# incandescentDriver.net
KiCad netlist of a schematic drawn in EAGLE
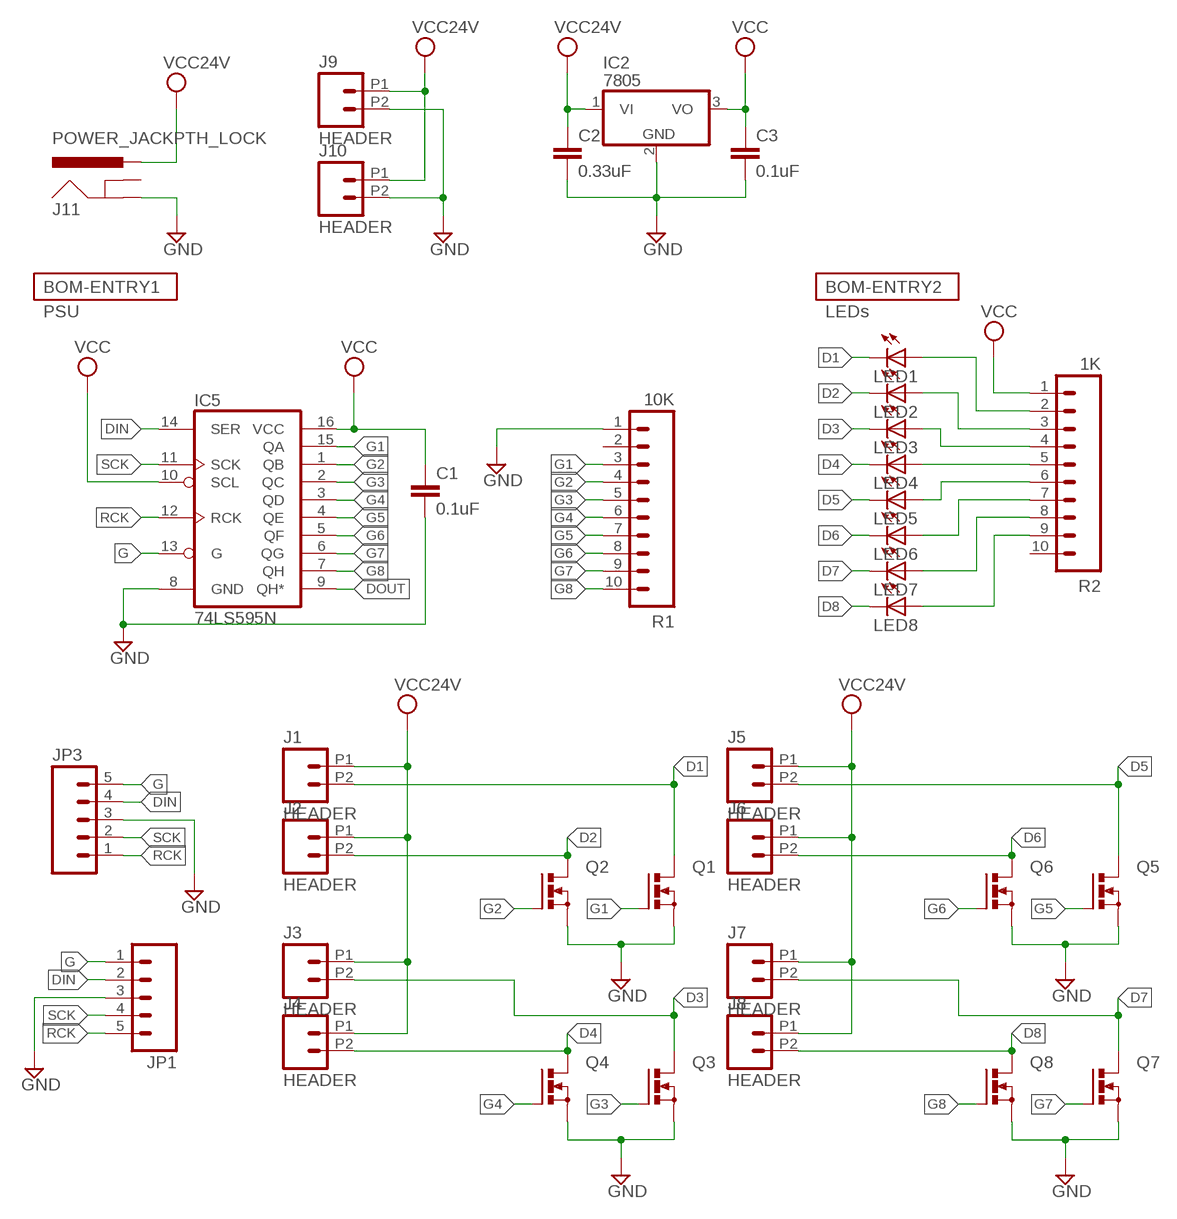
[diagram p0: schematic, sheet 1]

(export (version "E")
  (design (tool "Eeschema 10.0.6"))
  (components
    (comp (ref "C1")
      (value "0.1uF")
      (footprint "eagle-import:CAP-PTH-SMALL")
      (fields (field (name "PARTNO") "SR295E104MAR"))
      (libsource (lib "eagle-import") (part "CAPPTH"))
    )
    (comp (ref "C2")
      (value "0.33uF")
      (footprint "eagle-import:CAP-PTH-SMALL")
      (fields (field (name "PARTNO") "FK24X7R1H334K"))
      (libsource (lib "eagle-import") (part "CAPPTH"))
    )
    (comp (ref "C3")
      (value "0.1uF")
      (footprint "eagle-import:CAP-PTH-SMALL")
      (fields (field (name "PARTNO") "SR295E104MAR"))
      (libsource (lib "eagle-import") (part "CAPPTH"))
    )
    (comp (ref "IC2")
      (value "7805")
      (footprint "eagle-import:TO220V")
      (fields (field (name "PARTNO") "NCP7805TG"))
      (libsource (lib "eagle-import") (part "78TV8"))
    )
    (comp (ref "IC5")
      (value "74LS595N")
      (footprint "eagle-import:DIL16")
      (fields (field (name "PARTNO") "SN74HC164N"))
      (libsource (lib "eagle-import") (part "74595NLS"))
    )
    (comp (ref "J1")
      (value "HEADER")
      (footprint "eagle-import:1X02-5.08-SCREWTERM")
      (fields (field (name "PARTNO") "OSTTC022162"))
      (libsource (lib "eagle-import") (part "HEADER"))
    )
    (comp (ref "J2")
      (value "HEADER")
      (footprint "eagle-import:1X02-5.08-SCREWTERM")
      (fields (field (name "PARTNO") "OSTTC022162"))
      (libsource (lib "eagle-import") (part "HEADER"))
    )
    (comp (ref "J3")
      (value "HEADER")
      (footprint "eagle-import:1X02-5.08-SCREWTERM")
      (fields (field (name "PARTNO") "OSTTC022162"))
      (libsource (lib "eagle-import") (part "HEADER"))
    )
    (comp (ref "J4")
      (value "HEADER")
      (footprint "eagle-import:1X02-5.08-SCREWTERM")
      (fields (field (name "PARTNO") "OSTTC022162"))
      (libsource (lib "eagle-import") (part "HEADER"))
    )
    (comp (ref "J5")
      (value "HEADER")
      (footprint "eagle-import:1X02-5.08-SCREWTERM")
      (fields (field (name "PARTNO") "OSTTC022162"))
      (libsource (lib "eagle-import") (part "HEADER"))
    )
    (comp (ref "J6")
      (value "HEADER")
      (footprint "eagle-import:1X02-5.08-SCREWTERM")
      (fields (field (name "PARTNO") "OSTTC022162"))
      (libsource (lib "eagle-import") (part "HEADER"))
    )
    (comp (ref "J7")
      (value "HEADER")
      (footprint "eagle-import:1X02-5.08-SCREWTERM")
      (fields (field (name "PARTNO") "OSTTC022162"))
      (libsource (lib "eagle-import") (part "HEADER"))
    )
    (comp (ref "J8")
      (value "HEADER")
      (footprint "eagle-import:1X02-5.08-SCREWTERM")
      (fields (field (name "PARTNO") "OSTTC022162"))
      (libsource (lib "eagle-import") (part "HEADER"))
    )
    (comp (ref "J9")
      (value "HEADER")
      (footprint "eagle-import:1X02-5.08-SCREWTERM")
      (fields (field (name "PARTNO") "OSTTC022162"))
      (libsource (lib "eagle-import") (part "HEADER"))
    )
    (comp (ref "J10")
      (value "HEADER")
      (footprint "eagle-import:1X02-5.08-SCREWTERM")
      (fields (field (name "PARTNO") "OSTTC022162"))
      (libsource (lib "eagle-import") (part "HEADER"))
    )
    (comp (ref "J11")
      (value "POWER_JACKPTH_LOCK")
      (footprint "eagle-import:POWER_JACK_PTH_LOCK")
      (fields (field (name "PARTNO") "PJ-202A"))
      (libsource (lib "eagle-import") (part "POWER_JACKPTH_LOCK"))
    )
    (comp (ref "JP1")
      (value "M05LOCK")
      (footprint "eagle-import:1X05_LOCK")
      (fields (field (name "PARTNO") "M20-9960545"))
      (libsource (lib "eagle-import") (part "M05LOCK"))
    )
    (comp (ref "JP3")
      (value "M05LOCK")
      (footprint "eagle-import:1X05_LOCK")
      (fields (field (name "PARTNO") "M20-9960545"))
      (libsource (lib "eagle-import") (part "M05LOCK"))
    )
    (comp (ref "LED1")
      (value "LED5MM")
      (footprint "eagle-import:LED5MM")
      (libsource (lib "eagle-import") (part "LED5MM"))
    )
    (comp (ref "LED2")
      (value "LED5MM")
      (footprint "eagle-import:LED5MM")
      (libsource (lib "eagle-import") (part "LED5MM"))
    )
    (comp (ref "LED3")
      (value "LED5MM")
      (footprint "eagle-import:LED5MM")
      (libsource (lib "eagle-import") (part "LED5MM"))
    )
    (comp (ref "LED4")
      (value "LED5MM")
      (footprint "eagle-import:LED5MM")
      (libsource (lib "eagle-import") (part "LED5MM"))
    )
    (comp (ref "LED5")
      (value "LED5MM")
      (footprint "eagle-import:LED5MM")
      (libsource (lib "eagle-import") (part "LED5MM"))
    )
    (comp (ref "LED6")
      (value "LED5MM")
      (footprint "eagle-import:LED5MM")
      (libsource (lib "eagle-import") (part "LED5MM"))
    )
    (comp (ref "LED7")
      (value "LED5MM")
      (footprint "eagle-import:LED5MM")
      (libsource (lib "eagle-import") (part "LED5MM"))
    )
    (comp (ref "LED8")
      (value "LED5MM")
      (footprint "eagle-import:LED5MM")
      (libsource (lib "eagle-import") (part "LED5MM"))
    )
    (comp (ref "Q1")
      (value "PMOSFET_NTO220BV")
      (footprint "eagle-import:TO220BV")
      (fields (field (name "PARTNO") "FQP13N10L"))
      (libsource (lib "eagle-import") (part "PMOSFET_NTO220BV"))
    )
    (comp (ref "Q2")
      (value "PMOSFET_NTO220BV")
      (footprint "eagle-import:TO220BV")
      (fields (field (name "PARTNO") "FQP13N10L"))
      (libsource (lib "eagle-import") (part "PMOSFET_NTO220BV"))
    )
    (comp (ref "Q3")
      (value "PMOSFET_NTO220BV")
      (footprint "eagle-import:TO220BV")
      (fields (field (name "PARTNO") "FQP13N10L"))
      (libsource (lib "eagle-import") (part "PMOSFET_NTO220BV"))
    )
    (comp (ref "Q4")
      (value "PMOSFET_NTO220BV")
      (footprint "eagle-import:TO220BV")
      (fields (field (name "PARTNO") "FQP13N10L"))
      (libsource (lib "eagle-import") (part "PMOSFET_NTO220BV"))
    )
    (comp (ref "Q5")
      (value "PMOSFET_NTO220BV")
      (footprint "eagle-import:TO220BV")
      (fields (field (name "PARTNO") "FQP13N10L"))
      (libsource (lib "eagle-import") (part "PMOSFET_NTO220BV"))
    )
    (comp (ref "Q6")
      (value "PMOSFET_NTO220BV")
      (footprint "eagle-import:TO220BV")
      (fields (field (name "PARTNO") "FQP13N10L"))
      (libsource (lib "eagle-import") (part "PMOSFET_NTO220BV"))
    )
    (comp (ref "Q7")
      (value "PMOSFET_NTO220BV")
      (footprint "eagle-import:TO220BV")
      (fields (field (name "PARTNO") "FQP13N10L"))
      (libsource (lib "eagle-import") (part "PMOSFET_NTO220BV"))
    )
    (comp (ref "Q8")
      (value "PMOSFET_NTO220BV")
      (footprint "eagle-import:TO220BV")
      (fields (field (name "PARTNO") "FQP13N10L"))
      (libsource (lib "eagle-import") (part "PMOSFET_NTO220BV"))
    )
    (comp (ref "R1")
      (value "10K")
      (footprint "eagle-import:1X10_LOCK")
      (fields (field (name "PARTNO") "L101S103LF"))
      (libsource (lib "eagle-import") (part "M10LOCK"))
    )
    (comp (ref "R2")
      (value "1K")
      (footprint "eagle-import:1X10_LOCK")
      (fields (field (name "PARTNO") "4609X-101-102LF"))
      (libsource (lib "eagle-import") (part "M10LOCK"))
    )
  )
  (nets
    (net (code "1") (name "D1") (class "Default")
      (node (ref "J1") (pin "P2") (pinfunction "1_P2") (pintype "passive"))
      (node (ref "LED1") (pin "K") (pinfunction "C_K") (pintype "passive"))
      (node (ref "Q1") (pin "D") (pinfunction "D_D") (pintype "passive"))
    )
    (net (code "2") (name "D2") (class "Default")
      (node (ref "J2") (pin "P2") (pinfunction "1_P2") (pintype "passive"))
      (node (ref "LED2") (pin "K") (pinfunction "C_K") (pintype "passive"))
      (node (ref "Q2") (pin "D") (pinfunction "D_D") (pintype "passive"))
    )
    (net (code "3") (name "D3") (class "Default")
      (node (ref "J3") (pin "P2") (pinfunction "1_P2") (pintype "passive"))
      (node (ref "LED3") (pin "K") (pinfunction "C_K") (pintype "passive"))
      (node (ref "Q3") (pin "D") (pinfunction "D_D") (pintype "passive"))
    )
    (net (code "4") (name "D4") (class "Default")
      (node (ref "J4") (pin "P2") (pinfunction "1_P2") (pintype "passive"))
      (node (ref "LED4") (pin "K") (pinfunction "C_K") (pintype "passive"))
      (node (ref "Q4") (pin "D") (pinfunction "D_D") (pintype "passive"))
    )
    (net (code "5") (name "D5") (class "Default")
      (node (ref "J5") (pin "P2") (pinfunction "1_P2") (pintype "passive"))
      (node (ref "LED5") (pin "K") (pinfunction "C_K") (pintype "passive"))
      (node (ref "Q5") (pin "D") (pinfunction "D_D") (pintype "passive"))
    )
    (net (code "6") (name "D6") (class "Default")
      (node (ref "J6") (pin "P2") (pinfunction "1_P2") (pintype "passive"))
      (node (ref "LED6") (pin "K") (pinfunction "C_K") (pintype "passive"))
      (node (ref "Q6") (pin "D") (pinfunction "D_D") (pintype "passive"))
    )
    (net (code "7") (name "D7") (class "Default")
      (node (ref "J7") (pin "P2") (pinfunction "1_P2") (pintype "passive"))
      (node (ref "LED7") (pin "K") (pinfunction "C_K") (pintype "passive"))
      (node (ref "Q7") (pin "D") (pinfunction "D_D") (pintype "passive"))
    )
    (net (code "8") (name "D8") (class "Default")
      (node (ref "J8") (pin "P2") (pinfunction "1_P2") (pintype "passive"))
      (node (ref "LED8") (pin "K") (pinfunction "C_K") (pintype "passive"))
      (node (ref "Q8") (pin "D") (pinfunction "D_D") (pintype "passive"))
    )
    (net (code "9") (name "DIN") (class "Default")
      (node (ref "IC5") (pin "14") (pinfunction "SER_14") (pintype "input"))
      (node (ref "JP1") (pin "2") (pinfunction "2_2") (pintype "passive"))
      (node (ref "JP3") (pin "4") (pinfunction "4_4") (pintype "passive"))
    )
    (net (code "10") (name "DOUT") (class "Default")
      (node (ref "IC5") (pin "9") (pinfunction "QH*_9") (pintype "tri_state"))
    )
    (net (code "11") (name "G") (class "Default")
      (node (ref "IC5") (pin "13") (pinfunction "G_13") (pintype "input"))
      (node (ref "JP1") (pin "1") (pinfunction "1_1") (pintype "passive"))
      (node (ref "JP3") (pin "5") (pinfunction "5_5") (pintype "passive"))
    )
    (net (code "12") (name "G1") (class "Default")
      (node (ref "IC5") (pin "15") (pinfunction "QA_15") (pintype "tri_state"))
      (node (ref "Q1") (pin "G") (pinfunction "G_G") (pintype "passive"))
      (node (ref "R1") (pin "3") (pinfunction "3_3") (pintype "passive"))
    )
    (net (code "13") (name "G2") (class "Default")
      (node (ref "IC5") (pin "1") (pinfunction "QB_1") (pintype "tri_state"))
      (node (ref "Q2") (pin "G") (pinfunction "G_G") (pintype "passive"))
      (node (ref "R1") (pin "4") (pinfunction "4_4") (pintype "passive"))
    )
    (net (code "14") (name "G3") (class "Default")
      (node (ref "IC5") (pin "2") (pinfunction "QC_2") (pintype "tri_state"))
      (node (ref "Q3") (pin "G") (pinfunction "G_G") (pintype "passive"))
      (node (ref "R1") (pin "5") (pinfunction "5_5") (pintype "passive"))
    )
    (net (code "15") (name "G4") (class "Default")
      (node (ref "IC5") (pin "3") (pinfunction "QD_3") (pintype "tri_state"))
      (node (ref "Q4") (pin "G") (pinfunction "G_G") (pintype "passive"))
      (node (ref "R1") (pin "6") (pinfunction "6_6") (pintype "passive"))
    )
    (net (code "16") (name "G5") (class "Default")
      (node (ref "IC5") (pin "4") (pinfunction "QE_4") (pintype "tri_state"))
      (node (ref "Q5") (pin "G") (pinfunction "G_G") (pintype "passive"))
      (node (ref "R1") (pin "7") (pinfunction "7_7") (pintype "passive"))
    )
    (net (code "17") (name "G6") (class "Default")
      (node (ref "IC5") (pin "5") (pinfunction "QF_5") (pintype "tri_state"))
      (node (ref "Q6") (pin "G") (pinfunction "G_G") (pintype "passive"))
      (node (ref "R1") (pin "8") (pinfunction "8_8") (pintype "passive"))
    )
    (net (code "18") (name "G7") (class "Default")
      (node (ref "IC5") (pin "6") (pinfunction "QG_6") (pintype "tri_state"))
      (node (ref "Q7") (pin "G") (pinfunction "G_G") (pintype "passive"))
      (node (ref "R1") (pin "9") (pinfunction "9_9") (pintype "passive"))
    )
    (net (code "19") (name "G8") (class "Default")
      (node (ref "IC5") (pin "7") (pinfunction "QH_7") (pintype "tri_state"))
      (node (ref "Q8") (pin "G") (pinfunction "G_G") (pintype "passive"))
      (node (ref "R1") (pin "10") (pinfunction "10_10") (pintype "passive"))
    )
    (net (code "20") (name "GND") (class "Default")
      (node (ref "C1") (pin "2") (pinfunction "2_2") (pintype "passive"))
      (node (ref "C2") (pin "2") (pinfunction "2_2") (pintype "passive"))
      (node (ref "C3") (pin "2") (pinfunction "2_2") (pintype "passive"))
      (node (ref "IC2") (pin "2") (pinfunction "GND_2") (pintype "passive"))
      (node (ref "IC5") (pin "8") (pinfunction "GND_8") (pintype "power_in"))
      (node (ref "J10") (pin "P2") (pinfunction "1_P2") (pintype "passive"))
      (node (ref "J11") (pin "GND") (pinfunction "GND_GND") (pintype "bidirectional"))
      (node (ref "J9") (pin "P2") (pinfunction "1_P2") (pintype "passive"))
      (node (ref "JP1") (pin "3") (pinfunction "3_3") (pintype "passive"))
      (node (ref "JP3") (pin "3") (pinfunction "3_3") (pintype "passive"))
      (node (ref "Q1") (pin "S") (pinfunction "S_S") (pintype "passive"))
      (node (ref "Q2") (pin "S") (pinfunction "S_S") (pintype "passive"))
      (node (ref "Q3") (pin "S") (pinfunction "S_S") (pintype "passive"))
      (node (ref "Q4") (pin "S") (pinfunction "S_S") (pintype "passive"))
      (node (ref "Q5") (pin "S") (pinfunction "S_S") (pintype "passive"))
      (node (ref "Q6") (pin "S") (pinfunction "S_S") (pintype "passive"))
      (node (ref "Q7") (pin "S") (pinfunction "S_S") (pintype "passive"))
      (node (ref "Q8") (pin "S") (pinfunction "S_S") (pintype "passive"))
      (node (ref "R1") (pin "1") (pinfunction "1_1") (pintype "passive"))
    )
    (net (code "21") (name "Net-(LED1-PadA)") (class "Default")
      (node (ref "LED1") (pin "A") (pinfunction "A_A") (pintype "passive"))
      (node (ref "R2") (pin "2") (pinfunction "2_2") (pintype "passive"))
    )
    (net (code "22") (name "Net-(LED2-PadA)") (class "Default")
      (node (ref "LED2") (pin "A") (pinfunction "A_A") (pintype "passive"))
      (node (ref "R2") (pin "3") (pinfunction "3_3") (pintype "passive"))
    )
    (net (code "23") (name "Net-(LED3-PadA)") (class "Default")
      (node (ref "LED3") (pin "A") (pinfunction "A_A") (pintype "passive"))
      (node (ref "R2") (pin "4") (pinfunction "4_4") (pintype "passive"))
    )
    (net (code "24") (name "Net-(LED4-PadA)") (class "Default")
      (node (ref "LED4") (pin "A") (pinfunction "A_A") (pintype "passive"))
      (node (ref "R2") (pin "5") (pinfunction "5_5") (pintype "passive"))
    )
    (net (code "25") (name "Net-(LED5-PadA)") (class "Default")
      (node (ref "LED5") (pin "A") (pinfunction "A_A") (pintype "passive"))
      (node (ref "R2") (pin "6") (pinfunction "6_6") (pintype "passive"))
    )
    (net (code "26") (name "Net-(LED6-PadA)") (class "Default")
      (node (ref "LED6") (pin "A") (pinfunction "A_A") (pintype "passive"))
      (node (ref "R2") (pin "7") (pinfunction "7_7") (pintype "passive"))
    )
    (net (code "27") (name "Net-(LED7-PadA)") (class "Default")
      (node (ref "LED7") (pin "A") (pinfunction "A_A") (pintype "passive"))
      (node (ref "R2") (pin "8") (pinfunction "8_8") (pintype "passive"))
    )
    (net (code "28") (name "Net-(LED8-PadA)") (class "Default")
      (node (ref "LED8") (pin "A") (pinfunction "A_A") (pintype "passive"))
      (node (ref "R2") (pin "9") (pinfunction "9_9") (pintype "passive"))
    )
    (net (code "29") (name "RCK") (class "Default")
      (node (ref "IC5") (pin "12") (pinfunction "RCK_12") (pintype "input"))
      (node (ref "JP1") (pin "5") (pinfunction "5_5") (pintype "passive"))
      (node (ref "JP3") (pin "1") (pinfunction "1_1") (pintype "passive"))
    )
    (net (code "30") (name "SCK") (class "Default")
      (node (ref "IC5") (pin "11") (pinfunction "SCK_11") (pintype "input"))
      (node (ref "JP1") (pin "4") (pinfunction "4_4") (pintype "passive"))
      (node (ref "JP3") (pin "2") (pinfunction "2_2") (pintype "passive"))
    )
    (net (code "31") (name "VCC") (class "Default")
      (node (ref "C1") (pin "1") (pinfunction "1_1") (pintype "passive"))
      (node (ref "C3") (pin "1") (pinfunction "1_1") (pintype "passive"))
      (node (ref "IC2") (pin "3") (pinfunction "VO_3") (pintype "passive"))
      (node (ref "IC5") (pin "10") (pinfunction "SCL_10") (pintype "input"))
      (node (ref "IC5") (pin "16") (pinfunction "VCC_16") (pintype "power_in"))
      (node (ref "R2") (pin "1") (pinfunction "1_1") (pintype "passive"))
    )
    (net (code "32") (name "VCC24V") (class "Default")
      (node (ref "C2") (pin "1") (pinfunction "1_1") (pintype "passive"))
      (node (ref "IC2") (pin "1") (pinfunction "VI_1") (pintype "input"))
      (node (ref "J1") (pin "P1") (pinfunction "2_P1") (pintype "passive"))
      (node (ref "J10") (pin "P1") (pinfunction "2_P1") (pintype "passive"))
      (node (ref "J11") (pin "PWR") (pinfunction "PWR_PWR") (pintype "bidirectional"))
      (node (ref "J2") (pin "P1") (pinfunction "2_P1") (pintype "passive"))
      (node (ref "J3") (pin "P1") (pinfunction "2_P1") (pintype "passive"))
      (node (ref "J4") (pin "P1") (pinfunction "2_P1") (pintype "passive"))
      (node (ref "J5") (pin "P1") (pinfunction "2_P1") (pintype "passive"))
      (node (ref "J6") (pin "P1") (pinfunction "2_P1") (pintype "passive"))
      (node (ref "J7") (pin "P1") (pinfunction "2_P1") (pintype "passive"))
      (node (ref "J8") (pin "P1") (pinfunction "2_P1") (pintype "passive"))
      (node (ref "J9") (pin "P1") (pinfunction "2_P1") (pintype "passive"))
    )
    (net (code "33") (name "unconnected-(J11-PadGNDBREAK)") (class "Default")
      (node (ref "J11") (pin "GNDBREAK") (pinfunction "GNDBREAK_GNDBREAK") (pintype "bidirectional"))
    )
    (net (code "34") (name "unconnected-(R1-Pad2)") (class "Default")
      (node (ref "R1") (pin "2") (pinfunction "2_2") (pintype "passive"))
    )
    (net (code "35") (name "unconnected-(R2-Pad10)") (class "Default")
      (node (ref "R2") (pin "10") (pinfunction "10_10") (pintype "passive"))
    )
  )
)
